# due.net
KiCad netlist of a schematic drawn in EAGLE
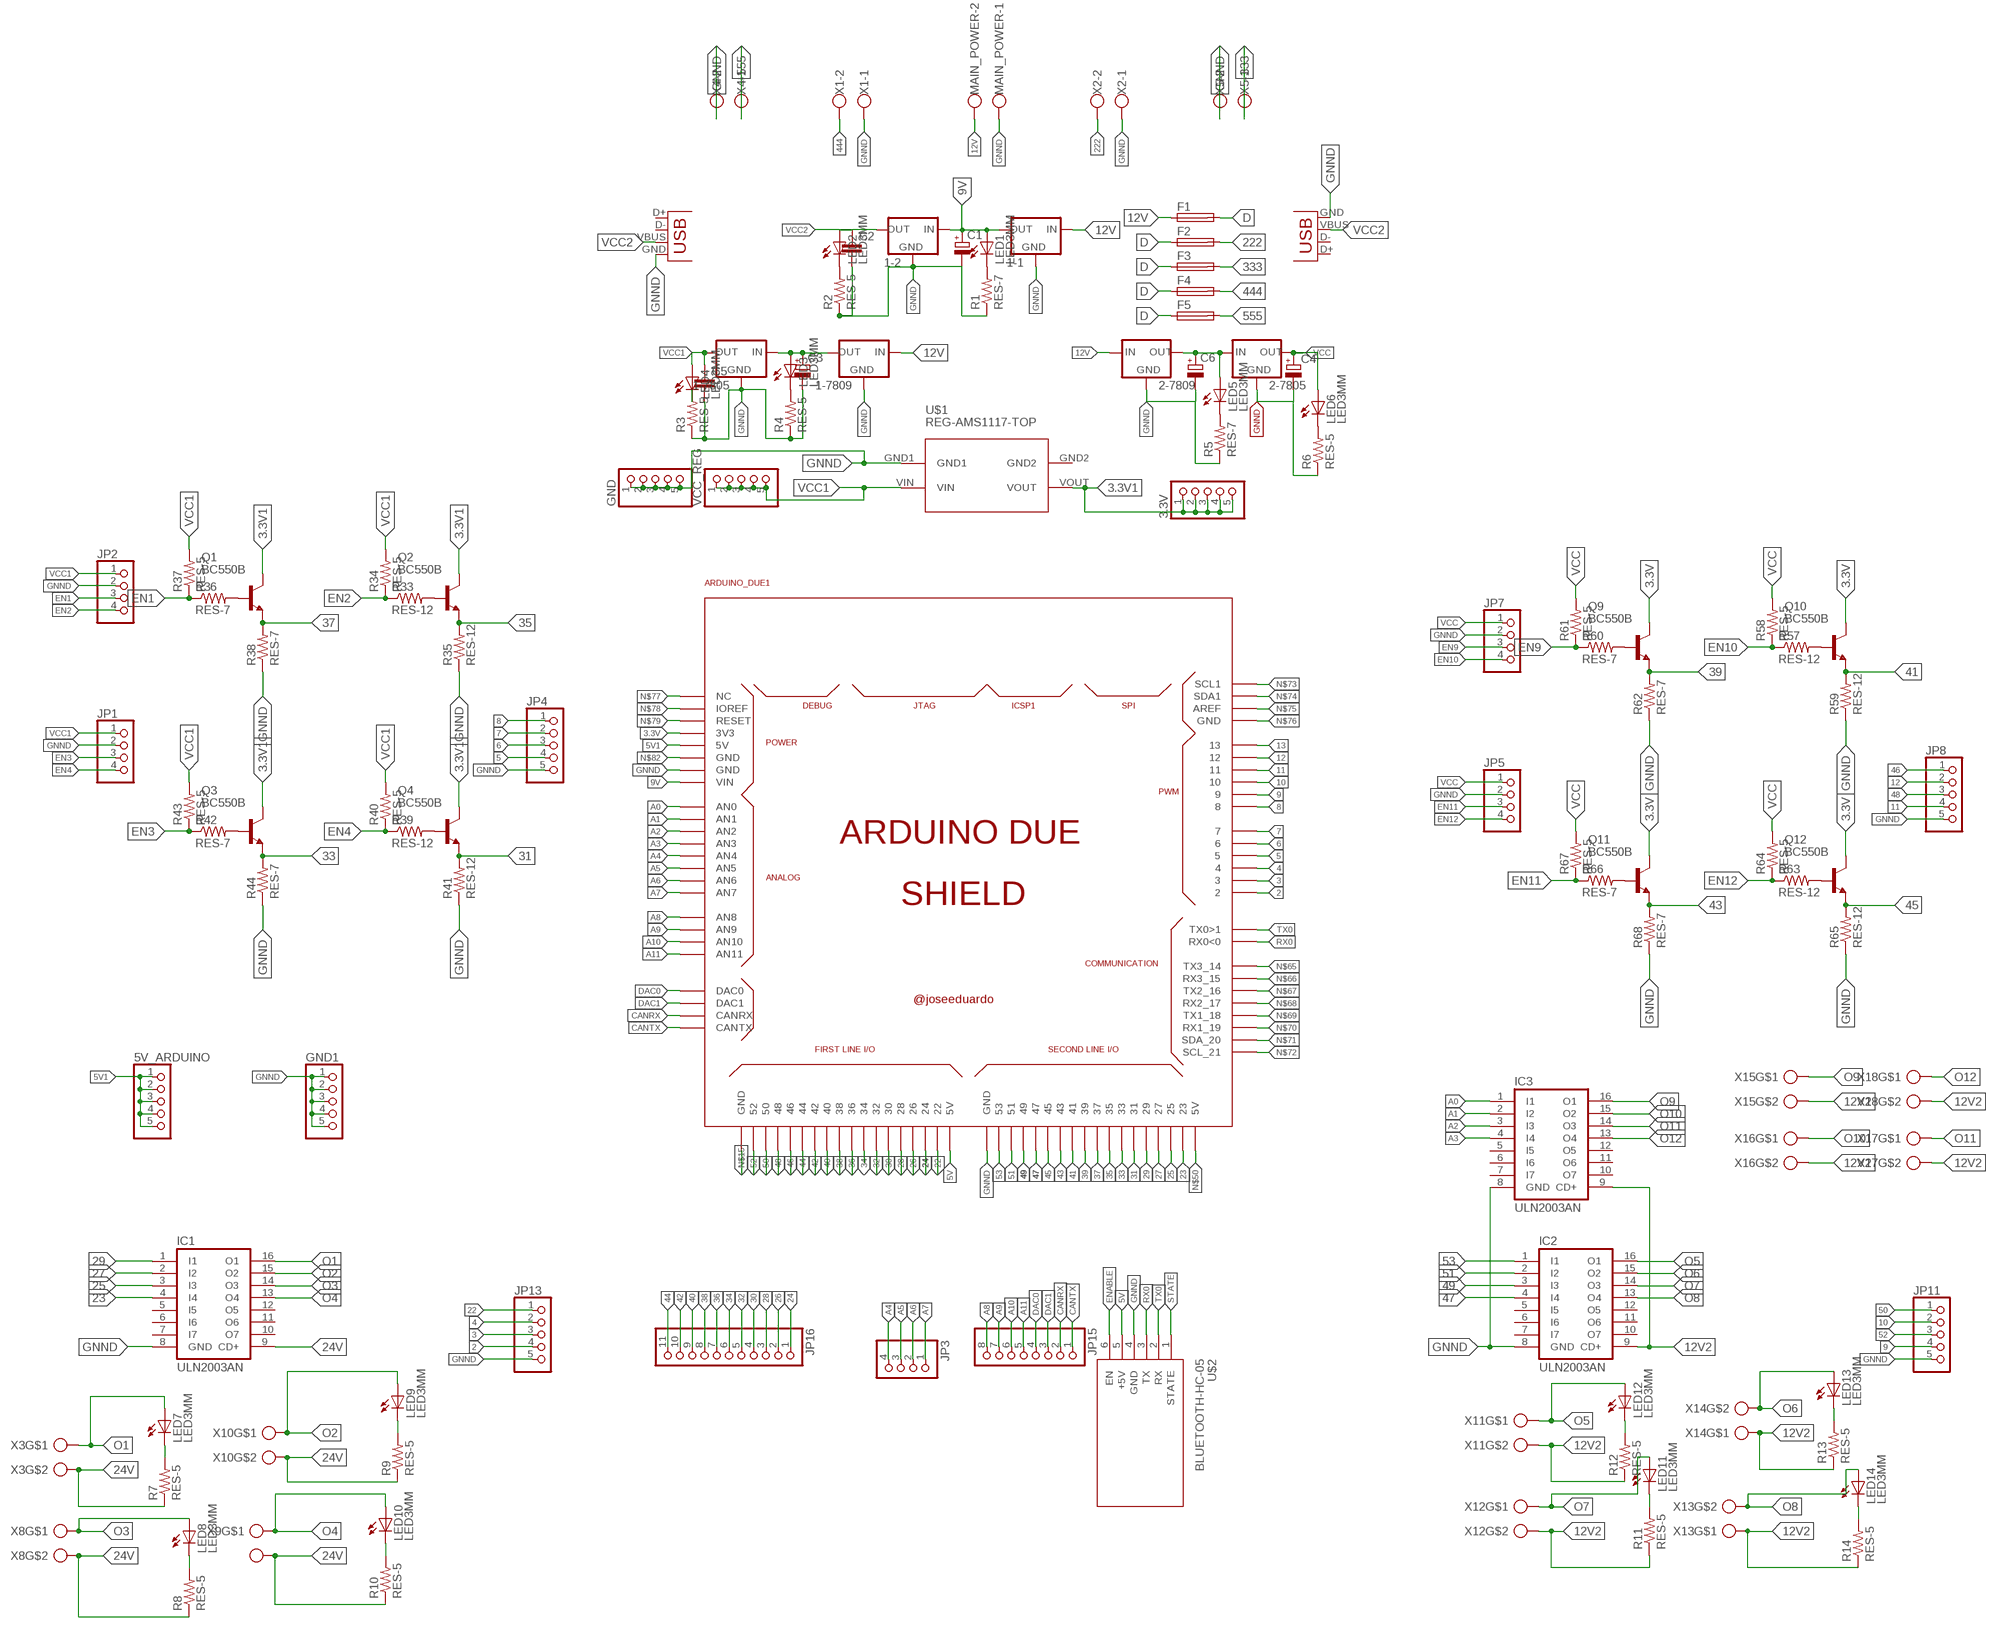
[diagram p0: schematic, sheet 1]

(export (version "E")
  (design (tool "Eeschema 10.0.6"))
  (components
    (comp (ref "1-1")
      (value "78XXS")
      (footprint "eagle-import:78XXS")
      (libsource (lib "eagle-import") (part "78XXS"))
    )
    (comp (ref "1-2")
      (value "78XXS")
      (footprint "eagle-import:78XXS")
      (libsource (lib "eagle-import") (part "78XXS"))
    )
    (comp (ref "1-7805")
      (value "78XXS")
      (footprint "eagle-import:78XXS")
      (libsource (lib "eagle-import") (part "78XXS"))
    )
    (comp (ref "1-7809")
      (value "78XXS")
      (footprint "eagle-import:78XXS")
      (libsource (lib "eagle-import") (part "78XXS"))
    )
    (comp (ref "2-7805")
      (value "78XXS")
      (footprint "eagle-import:78XXS")
      (libsource (lib "eagle-import") (part "78XXS"))
    )
    (comp (ref "2-7809")
      (value "78XXS")
      (footprint "eagle-import:78XXS")
      (libsource (lib "eagle-import") (part "78XXS"))
    )
    (comp (ref "3.3V")
      (value "PINHD-1X5")
      (footprint "eagle-import:1X05")
      (libsource (lib "eagle-import") (part "PINHD-1X5"))
    )
    (comp (ref "5V_ARDUINO")
      (value "PINHD-1X5")
      (footprint "eagle-import:1X05")
      (libsource (lib "eagle-import") (part "PINHD-1X5"))
    )
    (comp (ref "ARDUINO_DUE1")
      (value "ARDUINO_DUE_SHIELD")
      (footprint "eagle-import:ARDUINO_DUE_SHIELD")
      (libsource (lib "eagle-import") (part "ARDUINO_DUE_SHIELD"))
    )
    (comp (ref "C1")
      (value "CAP_POL")
      (footprint "eagle-import:E3,5-8")
      (libsource (lib "eagle-import") (part "CAP_POL"))
    )
    (comp (ref "C2")
      (value "CAPACITOR")
      (footprint "eagle-import:C025-025X050")
      (libsource (lib "eagle-import") (part "CAPACITOR"))
    )
    (comp (ref "C3")
      (value "CAP_POL")
      (footprint "eagle-import:E3,5-8")
      (libsource (lib "eagle-import") (part "CAP_POL"))
    )
    (comp (ref "C4")
      (value "CAP_POL")
      (footprint "eagle-import:E3,5-8")
      (libsource (lib "eagle-import") (part "CAP_POL"))
    )
    (comp (ref "C5")
      (value "CAPACITOR")
      (footprint "eagle-import:C025-025X050")
      (libsource (lib "eagle-import") (part "CAPACITOR"))
    )
    (comp (ref "C6")
      (value "CAP_POL")
      (footprint "eagle-import:E3,5-8")
      (libsource (lib "eagle-import") (part "CAP_POL"))
    )
    (comp (ref "F1")
      (value "FUSE_HOLDER")
      (footprint "eagle-import:SH22,5A")
      (libsource (lib "eagle-import") (part "FUSE_HOLDER"))
    )
    (comp (ref "F2")
      (value "FUSE_HOLDER")
      (footprint "eagle-import:SH22,5A")
      (libsource (lib "eagle-import") (part "FUSE_HOLDER"))
    )
    (comp (ref "F3")
      (value "FUSE_HOLDER")
      (footprint "eagle-import:SH22,5A")
      (libsource (lib "eagle-import") (part "FUSE_HOLDER"))
    )
    (comp (ref "F4")
      (value "FUSE_HOLDER")
      (footprint "eagle-import:SH22,5A")
      (libsource (lib "eagle-import") (part "FUSE_HOLDER"))
    )
    (comp (ref "F5")
      (value "FUSE_HOLDER")
      (footprint "eagle-import:SH22,5A")
      (libsource (lib "eagle-import") (part "FUSE_HOLDER"))
    )
    (comp (ref "GND")
      (value "PINHD-1X5")
      (footprint "eagle-import:1X05")
      (libsource (lib "eagle-import") (part "PINHD-1X5"))
    )
    (comp (ref "GND1")
      (value "PINHD-1X5")
      (footprint "eagle-import:1X05")
      (libsource (lib "eagle-import") (part "PINHD-1X5"))
    )
    (comp (ref "IC1")
      (value "ULN2003AN")
      (footprint "eagle-import:DIL16")
      (libsource (lib "eagle-import") (part "ULN2003AN"))
    )
    (comp (ref "IC2")
      (value "ULN2003AN")
      (footprint "eagle-import:DIL16")
      (libsource (lib "eagle-import") (part "ULN2003AN"))
    )
    (comp (ref "IC3")
      (value "ULN2003AN")
      (footprint "eagle-import:DIL16")
      (libsource (lib "eagle-import") (part "ULN2003AN"))
    )
    (comp (ref "JP1")
      (value "PINHD-1X4")
      (footprint "eagle-import:1X04")
      (libsource (lib "eagle-import") (part "PINHD-1X4"))
    )
    (comp (ref "JP2")
      (value "PINHD-1X4")
      (footprint "eagle-import:1X04")
      (libsource (lib "eagle-import") (part "PINHD-1X4"))
    )
    (comp (ref "JP3")
      (value "PINHD-1X4")
      (footprint "eagle-import:1X04")
      (libsource (lib "eagle-import") (part "PINHD-1X4"))
    )
    (comp (ref "JP4")
      (value "PINHD-1X5")
      (footprint "eagle-import:1X05")
      (libsource (lib "eagle-import") (part "PINHD-1X5"))
    )
    (comp (ref "JP5")
      (value "PINHD-1X4")
      (footprint "eagle-import:1X04")
      (libsource (lib "eagle-import") (part "PINHD-1X4"))
    )
    (comp (ref "JP7")
      (value "PINHD-1X4")
      (footprint "eagle-import:1X04")
      (libsource (lib "eagle-import") (part "PINHD-1X4"))
    )
    (comp (ref "JP8")
      (value "PINHD-1X5")
      (footprint "eagle-import:1X05")
      (libsource (lib "eagle-import") (part "PINHD-1X5"))
    )
    (comp (ref "JP11")
      (value "PINHD-1X5")
      (footprint "eagle-import:1X05")
      (libsource (lib "eagle-import") (part "PINHD-1X5"))
    )
    (comp (ref "JP13")
      (value "PINHD-1X5")
      (footprint "eagle-import:1X05")
      (libsource (lib "eagle-import") (part "PINHD-1X5"))
    )
    (comp (ref "JP15")
      (value "PINHD-1X8")
      (footprint "eagle-import:1X08")
      (libsource (lib "eagle-import") (part "PINHD-1X8"))
    )
    (comp (ref "JP16")
      (value "PINHD-1X11")
      (footprint "eagle-import:1X11")
      (libsource (lib "eagle-import") (part "PINHD-1X11"))
    )
    (comp (ref "LED1")
      (value "LED3MM")
      (footprint "eagle-import:LED3MM")
      (libsource (lib "eagle-import") (part "LED3MM"))
    )
    (comp (ref "LED2")
      (value "LED3MM")
      (footprint "eagle-import:LED3MM")
      (libsource (lib "eagle-import") (part "LED3MM"))
    )
    (comp (ref "LED3")
      (value "LED3MM")
      (footprint "eagle-import:LED3MM")
      (libsource (lib "eagle-import") (part "LED3MM"))
    )
    (comp (ref "LED4")
      (value "LED3MM")
      (footprint "eagle-import:LED3MM")
      (libsource (lib "eagle-import") (part "LED3MM"))
    )
    (comp (ref "LED5")
      (value "LED3MM")
      (footprint "eagle-import:LED3MM")
      (libsource (lib "eagle-import") (part "LED3MM"))
    )
    (comp (ref "LED6")
      (value "LED3MM")
      (footprint "eagle-import:LED3MM")
      (libsource (lib "eagle-import") (part "LED3MM"))
    )
    (comp (ref "LED7")
      (value "LED3MM")
      (footprint "eagle-import:LED3MM")
      (libsource (lib "eagle-import") (part "LED3MM"))
    )
    (comp (ref "LED8")
      (value "LED3MM")
      (footprint "eagle-import:LED3MM")
      (libsource (lib "eagle-import") (part "LED3MM"))
    )
    (comp (ref "LED9")
      (value "LED3MM")
      (footprint "eagle-import:LED3MM")
      (libsource (lib "eagle-import") (part "LED3MM"))
    )
    (comp (ref "LED10")
      (value "LED3MM")
      (footprint "eagle-import:LED3MM")
      (libsource (lib "eagle-import") (part "LED3MM"))
    )
    (comp (ref "LED11")
      (value "LED3MM")
      (footprint "eagle-import:LED3MM")
      (libsource (lib "eagle-import") (part "LED3MM"))
    )
    (comp (ref "LED12")
      (value "LED3MM")
      (footprint "eagle-import:LED3MM")
      (libsource (lib "eagle-import") (part "LED3MM"))
    )
    (comp (ref "LED13")
      (value "LED3MM")
      (footprint "eagle-import:LED3MM")
      (libsource (lib "eagle-import") (part "LED3MM"))
    )
    (comp (ref "LED14")
      (value "LED3MM")
      (footprint "eagle-import:LED3MM")
      (libsource (lib "eagle-import") (part "LED3MM"))
    )
    (comp (ref "MAIN_POWER")
      (value "ROSTA.POWER")
      (footprint "eagle-import:W239-302")
      (libsource (lib "eagle-import") (part "ROSTA.POWER"))
    )
    (comp (ref "Q1")
      (value "BC550B")
      (footprint "eagle-import:TO92-EBC")
      (libsource (lib "eagle-import") (part "BC550B"))
    )
    (comp (ref "Q2")
      (value "BC550B")
      (footprint "eagle-import:TO92-EBC")
      (libsource (lib "eagle-import") (part "BC550B"))
    )
    (comp (ref "Q3")
      (value "BC550B")
      (footprint "eagle-import:TO92-EBC")
      (libsource (lib "eagle-import") (part "BC550B"))
    )
    (comp (ref "Q4")
      (value "BC550B")
      (footprint "eagle-import:TO92-EBC")
      (libsource (lib "eagle-import") (part "BC550B"))
    )
    (comp (ref "Q9")
      (value "BC550B")
      (footprint "eagle-import:TO92-EBC")
      (libsource (lib "eagle-import") (part "BC550B"))
    )
    (comp (ref "Q10")
      (value "BC550B")
      (footprint "eagle-import:TO92-EBC")
      (libsource (lib "eagle-import") (part "BC550B"))
    )
    (comp (ref "Q11")
      (value "BC550B")
      (footprint "eagle-import:TO92-EBC")
      (libsource (lib "eagle-import") (part "BC550B"))
    )
    (comp (ref "Q12")
      (value "BC550B")
      (footprint "eagle-import:TO92-EBC")
      (libsource (lib "eagle-import") (part "BC550B"))
    )
    (comp (ref "R1")
      (value "RES-7")
      (footprint "eagle-import:0204_7")
      (libsource (lib "eagle-import") (part "RES-7"))
    )
    (comp (ref "R2")
      (value "RES-5")
      (footprint "eagle-import:0204_5")
      (libsource (lib "eagle-import") (part "RES-5"))
    )
    (comp (ref "R3")
      (value "RES-5")
      (footprint "eagle-import:0204_5")
      (libsource (lib "eagle-import") (part "RES-5"))
    )
    (comp (ref "R4")
      (value "RES-5")
      (footprint "eagle-import:0204_5")
      (libsource (lib "eagle-import") (part "RES-5"))
    )
    (comp (ref "R5")
      (value "RES-7")
      (footprint "eagle-import:0204_7")
      (libsource (lib "eagle-import") (part "RES-7"))
    )
    (comp (ref "R6")
      (value "RES-5")
      (footprint "eagle-import:0204_5")
      (libsource (lib "eagle-import") (part "RES-5"))
    )
    (comp (ref "R7")
      (value "RES-5")
      (footprint "eagle-import:0204_5")
      (libsource (lib "eagle-import") (part "RES-5"))
    )
    (comp (ref "R8")
      (value "RES-5")
      (footprint "eagle-import:0204_5")
      (libsource (lib "eagle-import") (part "RES-5"))
    )
    (comp (ref "R9")
      (value "RES-5")
      (footprint "eagle-import:0204_5")
      (libsource (lib "eagle-import") (part "RES-5"))
    )
    (comp (ref "R10")
      (value "RES-5")
      (footprint "eagle-import:0204_5")
      (libsource (lib "eagle-import") (part "RES-5"))
    )
    (comp (ref "R11")
      (value "RES-5")
      (footprint "eagle-import:0204_5")
      (libsource (lib "eagle-import") (part "RES-5"))
    )
    (comp (ref "R12")
      (value "RES-5")
      (footprint "eagle-import:0204_5")
      (libsource (lib "eagle-import") (part "RES-5"))
    )
    (comp (ref "R13")
      (value "RES-5")
      (footprint "eagle-import:0204_5")
      (libsource (lib "eagle-import") (part "RES-5"))
    )
    (comp (ref "R14")
      (value "RES-5")
      (footprint "eagle-import:0204_5")
      (libsource (lib "eagle-import") (part "RES-5"))
    )
    (comp (ref "R33")
      (value "RES-12")
      (footprint "eagle-import:0207_12")
      (libsource (lib "eagle-import") (part "RES-12"))
    )
    (comp (ref "R34")
      (value "RES-5")
      (footprint "eagle-import:0204_5")
      (libsource (lib "eagle-import") (part "RES-5"))
    )
    (comp (ref "R35")
      (value "RES-12")
      (footprint "eagle-import:0207_12")
      (libsource (lib "eagle-import") (part "RES-12"))
    )
    (comp (ref "R36")
      (value "RES-7")
      (footprint "eagle-import:0204_7")
      (libsource (lib "eagle-import") (part "RES-7"))
    )
    (comp (ref "R37")
      (value "RES-5")
      (footprint "eagle-import:0204_5")
      (libsource (lib "eagle-import") (part "RES-5"))
    )
    (comp (ref "R38")
      (value "RES-7")
      (footprint "eagle-import:0204_7")
      (libsource (lib "eagle-import") (part "RES-7"))
    )
    (comp (ref "R39")
      (value "RES-12")
      (footprint "eagle-import:0207_12")
      (libsource (lib "eagle-import") (part "RES-12"))
    )
    (comp (ref "R40")
      (value "RES-5")
      (footprint "eagle-import:0204_5")
      (libsource (lib "eagle-import") (part "RES-5"))
    )
    (comp (ref "R41")
      (value "RES-12")
      (footprint "eagle-import:0207_12")
      (libsource (lib "eagle-import") (part "RES-12"))
    )
    (comp (ref "R42")
      (value "RES-7")
      (footprint "eagle-import:0204_7")
      (libsource (lib "eagle-import") (part "RES-7"))
    )
    (comp (ref "R43")
      (value "RES-5")
      (footprint "eagle-import:0204_5")
      (libsource (lib "eagle-import") (part "RES-5"))
    )
    (comp (ref "R44")
      (value "RES-7")
      (footprint "eagle-import:0204_7")
      (libsource (lib "eagle-import") (part "RES-7"))
    )
    (comp (ref "R57")
      (value "RES-12")
      (footprint "eagle-import:0207_12")
      (libsource (lib "eagle-import") (part "RES-12"))
    )
    (comp (ref "R58")
      (value "RES-5")
      (footprint "eagle-import:0204_5")
      (libsource (lib "eagle-import") (part "RES-5"))
    )
    (comp (ref "R59")
      (value "RES-12")
      (footprint "eagle-import:0207_12")
      (libsource (lib "eagle-import") (part "RES-12"))
    )
    (comp (ref "R60")
      (value "RES-7")
      (footprint "eagle-import:0204_7")
      (libsource (lib "eagle-import") (part "RES-7"))
    )
    (comp (ref "R61")
      (value "RES-5")
      (footprint "eagle-import:0204_5")
      (libsource (lib "eagle-import") (part "RES-5"))
    )
    (comp (ref "R62")
      (value "RES-7")
      (footprint "eagle-import:0204_7")
      (libsource (lib "eagle-import") (part "RES-7"))
    )
    (comp (ref "R63")
      (value "RES-12")
      (footprint "eagle-import:0207_12")
      (libsource (lib "eagle-import") (part "RES-12"))
    )
    (comp (ref "R64")
      (value "RES-5")
      (footprint "eagle-import:0204_5")
      (libsource (lib "eagle-import") (part "RES-5"))
    )
    (comp (ref "R65")
      (value "RES-12")
      (footprint "eagle-import:0207_12")
      (libsource (lib "eagle-import") (part "RES-12"))
    )
    (comp (ref "R66")
      (value "RES-7")
      (footprint "eagle-import:0204_7")
      (libsource (lib "eagle-import") (part "RES-7"))
    )
    (comp (ref "R67")
      (value "RES-5")
      (footprint "eagle-import:0204_5")
      (libsource (lib "eagle-import") (part "RES-5"))
    )
    (comp (ref "R68")
      (value "RES-7")
      (footprint "eagle-import:0204_7")
      (libsource (lib "eagle-import") (part "RES-7"))
    )
    (comp (ref "U$1")
      (value "REG-AMS1117-TOP")
      (footprint "eagle-import:REG-AMS1117_TOP")
      (libsource (lib "eagle-import") (part "REG-AMS1117-TOP"))
    )
    (comp (ref "U$2")
      (value "BLUETOOTH-HC-05")
      (footprint "eagle-import:WIRELESS-BLUETOOTH-HC-05")
      (libsource (lib "eagle-import") (part "BLUETOOTH-HC-05"))
    )
    (comp (ref "VCC_REG")
      (value "PINHD-1X5")
      (footprint "eagle-import:1X05")
      (libsource (lib "eagle-import") (part "PINHD-1X5"))
    )
    (comp (ref "X1")
      (value "ROSTA.POWER")
      (footprint "eagle-import:W239-302")
      (libsource (lib "eagle-import") (part "ROSTA.POWER"))
    )
    (comp (ref "X2")
      (value "ROSTA.POWER")
      (footprint "eagle-import:W239-302")
      (libsource (lib "eagle-import") (part "ROSTA.POWER"))
    )
    (comp (ref "X3")
      (value "CON_PTR_2")
      (footprint "eagle-import:AK300_2")
      (libsource (lib "eagle-import") (part "CON_PTR_2"))
    )
    (comp (ref "X4")
      (value "ROSTA.POWER")
      (footprint "eagle-import:W239-302")
      (libsource (lib "eagle-import") (part "ROSTA.POWER"))
    )
    (comp (ref "X5")
      (value "ROSTA.POWER")
      (footprint "eagle-import:W239-302")
      (libsource (lib "eagle-import") (part "ROSTA.POWER"))
    )
    (comp (ref "X6")
      (value "USB-A-H")
      (footprint "eagle-import:USB-A-H")
      (libsource (lib "eagle-import") (part "USB-A-H"))
    )
    (comp (ref "X7")
      (value "USB-A-H")
      (footprint "eagle-import:USB-A-H")
      (libsource (lib "eagle-import") (part "USB-A-H"))
    )
    (comp (ref "X8")
      (value "CON_PTR_2")
      (footprint "eagle-import:AK300_2")
      (libsource (lib "eagle-import") (part "CON_PTR_2"))
    )
    (comp (ref "X9")
      (value "CON_PTR_2")
      (footprint "eagle-import:AK300_2")
      (libsource (lib "eagle-import") (part "CON_PTR_2"))
    )
    (comp (ref "X10")
      (value "CON_PTR_2")
      (footprint "eagle-import:AK300_2")
      (libsource (lib "eagle-import") (part "CON_PTR_2"))
    )
    (comp (ref "X11")
      (value "CON_PTR_2")
      (footprint "eagle-import:AK300_2")
      (libsource (lib "eagle-import") (part "CON_PTR_2"))
    )
    (comp (ref "X12")
      (value "CON_PTR_2")
      (footprint "eagle-import:AK300_2")
      (libsource (lib "eagle-import") (part "CON_PTR_2"))
    )
    (comp (ref "X13")
      (value "CON_PTR_2")
      (footprint "eagle-import:AK300_2")
      (libsource (lib "eagle-import") (part "CON_PTR_2"))
    )
    (comp (ref "X14")
      (value "CON_PTR_2")
      (footprint "eagle-import:AK300_2")
      (libsource (lib "eagle-import") (part "CON_PTR_2"))
    )
    (comp (ref "X15")
      (value "CON_PTR_2")
      (footprint "eagle-import:AK300_2")
      (libsource (lib "eagle-import") (part "CON_PTR_2"))
    )
    (comp (ref "X16")
      (value "CON_PTR_2")
      (footprint "eagle-import:AK300_2")
      (libsource (lib "eagle-import") (part "CON_PTR_2"))
    )
    (comp (ref "X17")
      (value "CON_PTR_2")
      (footprint "eagle-import:AK300_2")
      (libsource (lib "eagle-import") (part "CON_PTR_2"))
    )
    (comp (ref "X18")
      (value "CON_PTR_2")
      (footprint "eagle-import:AK300_2")
      (libsource (lib "eagle-import") (part "CON_PTR_2"))
    )
  )
  (nets
    (net (code "1") (name "2") (class "Default")
      (node (ref "ARDUINO_DUE1") (pin "2") (pinfunction "2_2") (pintype "bidirectional"))
      (node (ref "JP13") (pin "4") (pinfunction "4_4") (pintype "passive"))
    )
    (net (code "2") (name "3") (class "Default")
      (node (ref "ARDUINO_DUE1") (pin "3") (pinfunction "3_3") (pintype "bidirectional"))
      (node (ref "JP13") (pin "3") (pinfunction "3_3") (pintype "passive"))
    )
    (net (code "3") (name "3.3V") (class "Default")
      (node (ref "ARDUINO_DUE1") (pin "3V3") (pinfunction "3V3_3V3") (pintype "bidirectional"))
      (node (ref "Q10") (pin "C") (pinfunction "C_C") (pintype "passive"))
      (node (ref "Q11") (pin "C") (pinfunction "C_C") (pintype "passive"))
      (node (ref "Q12") (pin "C") (pinfunction "C_C") (pintype "passive"))
      (node (ref "Q9") (pin "C") (pinfunction "C_C") (pintype "passive"))
    )
    (net (code "4") (name "3.3V1") (class "Default")
      (node (ref "3.3V") (pin "1") (pinfunction "1_1") (pintype "passive"))
      (node (ref "3.3V") (pin "2") (pinfunction "2_2") (pintype "passive"))
      (node (ref "3.3V") (pin "3") (pinfunction "3_3") (pintype "passive"))
      (node (ref "3.3V") (pin "4") (pinfunction "4_4") (pintype "passive"))
      (node (ref "3.3V") (pin "5") (pinfunction "5_5") (pintype "passive"))
      (node (ref "Q1") (pin "C") (pinfunction "C_C") (pintype "passive"))
      (node (ref "Q2") (pin "C") (pinfunction "C_C") (pintype "passive"))
      (node (ref "Q3") (pin "C") (pinfunction "C_C") (pintype "passive"))
      (node (ref "Q4") (pin "C") (pinfunction "C_C") (pintype "passive"))
      (node (ref "U$1") (pin "VOUT") (pinfunction "VOUT_VOUT") (pintype "bidirectional"))
    )
    (net (code "5") (name "4") (class "Default")
      (node (ref "ARDUINO_DUE1") (pin "4") (pinfunction "4_4") (pintype "bidirectional"))
      (node (ref "JP13") (pin "2") (pinfunction "2_2") (pintype "passive"))
    )
    (net (code "6") (name "5") (class "Default")
      (node (ref "ARDUINO_DUE1") (pin "5") (pinfunction "5_5") (pintype "bidirectional"))
      (node (ref "JP4") (pin "4") (pinfunction "4_4") (pintype "passive"))
    )
    (net (code "7") (name "5V") (class "Default")
      (node (ref "ARDUINO_DUE1") (pin "5V0_1") (pinfunction "5V_5V0_1") (pintype "bidirectional"))
      (node (ref "U$2") (pin "5") (pinfunction "+5V_5") (pintype "power_in"))
    )
    (net (code "8") (name "5V1") (class "Default")
      (node (ref "5V_ARDUINO") (pin "1") (pinfunction "1_1") (pintype "passive"))
      (node (ref "5V_ARDUINO") (pin "2") (pinfunction "2_2") (pintype "passive"))
      (node (ref "5V_ARDUINO") (pin "3") (pinfunction "3_3") (pintype "passive"))
      (node (ref "5V_ARDUINO") (pin "4") (pinfunction "4_4") (pintype "passive"))
      (node (ref "5V_ARDUINO") (pin "5") (pinfunction "5_5") (pintype "passive"))
      (node (ref "ARDUINO_DUE1") (pin "5V0") (pinfunction "5V_5V0") (pintype "bidirectional"))
    )
    (net (code "9") (name "6") (class "Default")
      (node (ref "ARDUINO_DUE1") (pin "6") (pinfunction "6_6") (pintype "bidirectional"))
      (node (ref "JP4") (pin "3") (pinfunction "3_3") (pintype "passive"))
    )
    (net (code "10") (name "7") (class "Default")
      (node (ref "ARDUINO_DUE1") (pin "7") (pinfunction "7_7") (pintype "bidirectional"))
      (node (ref "JP4") (pin "2") (pinfunction "2_2") (pintype "passive"))
    )
    (net (code "11") (name "8") (class "Default")
      (node (ref "ARDUINO_DUE1") (pin "8") (pinfunction "8_8") (pintype "bidirectional"))
      (node (ref "JP4") (pin "1") (pinfunction "1_1") (pintype "passive"))
    )
    (net (code "12") (name "9") (class "Default")
      (node (ref "ARDUINO_DUE1") (pin "9") (pinfunction "9_9") (pintype "bidirectional"))
      (node (ref "JP11") (pin "4") (pinfunction "4_4") (pintype "passive"))
    )
    (net (code "13") (name "9V") (class "Default")
      (node (ref "1-1") (pin "OUT") (pinfunction "OUT_OUT") (pintype "passive"))
      (node (ref "1-2") (pin "IN") (pinfunction "IN_IN") (pintype "input"))
      (node (ref "ARDUINO_DUE1") (pin "VIN") (pinfunction "VIN_VIN") (pintype "bidirectional"))
      (node (ref "C1") (pin "+") (pinfunction "+_+") (pintype "passive"))
      (node (ref "LED1") (pin "A") (pinfunction "A_A") (pintype "passive"))
    )
    (net (code "14") (name "10") (class "Default")
      (node (ref "ARDUINO_DUE1") (pin "10") (pinfunction "10_10") (pintype "bidirectional"))
      (node (ref "JP11") (pin "2") (pinfunction "2_2") (pintype "passive"))
    )
    (net (code "15") (name "11") (class "Default")
      (node (ref "ARDUINO_DUE1") (pin "11") (pinfunction "11_11") (pintype "bidirectional"))
      (node (ref "JP8") (pin "4") (pinfunction "4_4") (pintype "passive"))
    )
    (net (code "16") (name "12") (class "Default")
      (node (ref "ARDUINO_DUE1") (pin "12") (pinfunction "12_12") (pintype "bidirectional"))
      (node (ref "JP8") (pin "2") (pinfunction "2_2") (pintype "passive"))
    )
    (net (code "17") (name "12V") (class "Default")
      (node (ref "1-1") (pin "IN") (pinfunction "IN_IN") (pintype "input"))
      (node (ref "1-7809") (pin "IN") (pinfunction "IN_IN") (pintype "input"))
      (node (ref "2-7809") (pin "IN") (pinfunction "IN_IN") (pintype "input"))
      (node (ref "F1") (pin "1") (pinfunction "1_1") (pintype "passive"))
      (node (ref "MAIN_POWER") (pin "2") (pinfunction "KL_2") (pintype "passive"))
    )
    (net (code "18") (name "12V2") (class "Default")
      (node (ref "IC2") (pin "9") (pinfunction "CD+_9") (pintype "passive"))
      (node (ref "IC3") (pin "9") (pinfunction "CD+_9") (pintype "passive"))
      (node (ref "R11") (pin "1") (pinfunction "1_1") (pintype "passive"))
      (node (ref "R12") (pin "1") (pinfunction "1_1") (pintype "passive"))
      (node (ref "R13") (pin "1") (pinfunction "1_1") (pintype "passive"))
      (node (ref "R14") (pin "1") (pinfunction "1_1") (pintype "passive"))
      (node (ref "X11") (pin "2") (pinfunction "KL_2") (pintype "passive"))
      (node (ref "X12") (pin "2") (pinfunction "KL_2") (pintype "passive"))
      (node (ref "X13") (pin "1") (pinfunction "KL_1") (pintype "passive"))
      (node (ref "X14") (pin "1") (pinfunction "KL_1") (pintype "passive"))
      (node (ref "X15") (pin "2") (pinfunction "KL_2") (pintype "passive"))
      (node (ref "X16") (pin "2") (pinfunction "KL_2") (pintype "passive"))
      (node (ref "X17") (pin "2") (pinfunction "KL_2") (pintype "passive"))
      (node (ref "X18") (pin "2") (pinfunction "KL_2") (pintype "passive"))
    )
    (net (code "19") (name "13") (class "Default")
      (node (ref "ARDUINO_DUE1") (pin "13") (pinfunction "13_13") (pintype "bidirectional"))
    )
    (net (code "20") (name "22") (class "Default")
      (node (ref "ARDUINO_DUE1") (pin "22") (pinfunction "22_22") (pintype "bidirectional"))
      (node (ref "JP13") (pin "1") (pinfunction "1_1") (pintype "passive"))
    )
    (net (code "21") (name "23") (class "Default")
      (node (ref "ARDUINO_DUE1") (pin "23") (pinfunction "23_23") (pintype "bidirectional"))
      (node (ref "IC1") (pin "4") (pinfunction "I4_4") (pintype "input"))
    )
    (net (code "22") (name "24") (class "Default")
      (node (ref "ARDUINO_DUE1") (pin "24") (pinfunction "24_24") (pintype "bidirectional"))
      (node (ref "JP16") (pin "1") (pinfunction "1_1") (pintype "passive"))
    )
    (net (code "23") (name "24V") (class "Default")
      (node (ref "IC1") (pin "9") (pinfunction "CD+_9") (pintype "passive"))
      (node (ref "R10") (pin "1") (pinfunction "1_1") (pintype "passive"))
      (node (ref "R7") (pin "1") (pinfunction "1_1") (pintype "passive"))
      (node (ref "R8") (pin "1") (pinfunction "1_1") (pintype "passive"))
      (node (ref "R9") (pin "1") (pinfunction "1_1") (pintype "passive"))
      (node (ref "X10") (pin "2") (pinfunction "KL_2") (pintype "passive"))
      (node (ref "X3") (pin "2") (pinfunction "KL_2") (pintype "passive"))
      (node (ref "X8") (pin "2") (pinfunction "KL_2") (pintype "passive"))
      (node (ref "X9") (pin "2") (pinfunction "KL_2") (pintype "passive"))
    )
    (net (code "24") (name "25") (class "Default")
      (node (ref "ARDUINO_DUE1") (pin "25") (pinfunction "25_25") (pintype "bidirectional"))
      (node (ref "IC1") (pin "3") (pinfunction "I3_3") (pintype "input"))
    )
    (net (code "25") (name "26") (class "Default")
      (node (ref "ARDUINO_DUE1") (pin "26") (pinfunction "26_26") (pintype "bidirectional"))
      (node (ref "JP16") (pin "2") (pinfunction "2_2") (pintype "passive"))
    )
    (net (code "26") (name "27") (class "Default")
      (node (ref "ARDUINO_DUE1") (pin "27") (pinfunction "27_27") (pintype "bidirectional"))
      (node (ref "IC1") (pin "2") (pinfunction "I2_2") (pintype "input"))
    )
    (net (code "27") (name "28") (class "Default")
      (node (ref "ARDUINO_DUE1") (pin "28") (pinfunction "28_28") (pintype "bidirectional"))
      (node (ref "JP16") (pin "3") (pinfunction "3_3") (pintype "passive"))
    )
    (net (code "28") (name "29") (class "Default")
      (node (ref "ARDUINO_DUE1") (pin "29") (pinfunction "29_29") (pintype "bidirectional"))
      (node (ref "IC1") (pin "1") (pinfunction "I1_1") (pintype "input"))
    )
    (net (code "29") (name "30") (class "Default")
      (node (ref "ARDUINO_DUE1") (pin "30") (pinfunction "30_30") (pintype "bidirectional"))
      (node (ref "JP16") (pin "4") (pinfunction "4_4") (pintype "passive"))
    )
    (net (code "30") (name "31") (class "Default")
      (node (ref "ARDUINO_DUE1") (pin "31") (pinfunction "31_31") (pintype "bidirectional"))
      (node (ref "Q4") (pin "E") (pinfunction "E_E") (pintype "passive"))
      (node (ref "R41") (pin "2") (pinfunction "2_2") (pintype "passive"))
    )
    (net (code "31") (name "32") (class "Default")
      (node (ref "ARDUINO_DUE1") (pin "32") (pinfunction "32_32") (pintype "bidirectional"))
      (node (ref "JP16") (pin "5") (pinfunction "5_5") (pintype "passive"))
    )
    (net (code "32") (name "33") (class "Default")
      (node (ref "ARDUINO_DUE1") (pin "33") (pinfunction "33_33") (pintype "bidirectional"))
      (node (ref "Q3") (pin "E") (pinfunction "E_E") (pintype "passive"))
      (node (ref "R44") (pin "2") (pinfunction "2_2") (pintype "passive"))
    )
    (net (code "33") (name "34") (class "Default")
      (node (ref "ARDUINO_DUE1") (pin "34") (pinfunction "34_34") (pintype "bidirectional"))
      (node (ref "JP16") (pin "6") (pinfunction "6_6") (pintype "passive"))
    )
    (net (code "34") (name "35") (class "Default")
      (node (ref "ARDUINO_DUE1") (pin "35") (pinfunction "35_35") (pintype "bidirectional"))
      (node (ref "Q2") (pin "E") (pinfunction "E_E") (pintype "passive"))
      (node (ref "R35") (pin "2") (pinfunction "2_2") (pintype "passive"))
    )
    (net (code "35") (name "36") (class "Default")
      (node (ref "ARDUINO_DUE1") (pin "36") (pinfunction "36_36") (pintype "bidirectional"))
      (node (ref "JP16") (pin "7") (pinfunction "7_7") (pintype "passive"))
    )
    (net (code "36") (name "37") (class "Default")
      (node (ref "ARDUINO_DUE1") (pin "37") (pinfunction "37_37") (pintype "bidirectional"))
      (node (ref "Q1") (pin "E") (pinfunction "E_E") (pintype "passive"))
      (node (ref "R38") (pin "2") (pinfunction "2_2") (pintype "passive"))
    )
    (net (code "37") (name "38") (class "Default")
      (node (ref "ARDUINO_DUE1") (pin "38") (pinfunction "38_38") (pintype "bidirectional"))
      (node (ref "JP16") (pin "8") (pinfunction "8_8") (pintype "passive"))
    )
    (net (code "38") (name "39") (class "Default")
      (node (ref "ARDUINO_DUE1") (pin "39") (pinfunction "39_39") (pintype "bidirectional"))
      (node (ref "Q9") (pin "E") (pinfunction "E_E") (pintype "passive"))
      (node (ref "R62") (pin "2") (pinfunction "2_2") (pintype "passive"))
    )
    (net (code "39") (name "40") (class "Default")
      (node (ref "ARDUINO_DUE1") (pin "40") (pinfunction "40_40") (pintype "bidirectional"))
      (node (ref "JP16") (pin "9") (pinfunction "9_9") (pintype "passive"))
    )
    (net (code "40") (name "41") (class "Default")
      (node (ref "ARDUINO_DUE1") (pin "41") (pinfunction "41_41") (pintype "bidirectional"))
      (node (ref "Q10") (pin "E") (pinfunction "E_E") (pintype "passive"))
      (node (ref "R59") (pin "2") (pinfunction "2_2") (pintype "passive"))
    )
    (net (code "41") (name "42") (class "Default")
      (node (ref "ARDUINO_DUE1") (pin "42") (pinfunction "42_42") (pintype "bidirectional"))
      (node (ref "JP16") (pin "10") (pinfunction "10_10") (pintype "passive"))
    )
    (net (code "42") (name "43") (class "Default")
      (node (ref "ARDUINO_DUE1") (pin "43") (pinfunction "43_43") (pintype "bidirectional"))
      (node (ref "Q11") (pin "E") (pinfunction "E_E") (pintype "passive"))
      (node (ref "R68") (pin "2") (pinfunction "2_2") (pintype "passive"))
    )
    (net (code "43") (name "44") (class "Default")
      (node (ref "ARDUINO_DUE1") (pin "44") (pinfunction "44_44") (pintype "bidirectional"))
      (node (ref "JP16") (pin "11") (pinfunction "11_11") (pintype "passive"))
    )
    (net (code "44") (name "45") (class "Default")
      (node (ref "ARDUINO_DUE1") (pin "45") (pinfunction "45_45") (pintype "bidirectional"))
      (node (ref "Q12") (pin "E") (pinfunction "E_E") (pintype "passive"))
      (node (ref "R65") (pin "2") (pinfunction "2_2") (pintype "passive"))
    )
    (net (code "45") (name "46") (class "Default")
      (node (ref "ARDUINO_DUE1") (pin "46") (pinfunction "46_46") (pintype "bidirectional"))
      (node (ref "JP8") (pin "1") (pinfunction "1_1") (pintype "passive"))
    )
    (net (code "46") (name "47") (class "Default")
      (node (ref "ARDUINO_DUE1") (pin "47") (pinfunction "47_47") (pintype "bidirectional"))
      (node (ref "IC2") (pin "4") (pinfunction "I4_4") (pintype "input"))
    )
    (net (code "47") (name "48") (class "Default")
      (node (ref "ARDUINO_DUE1") (pin "48") (pinfunction "48_48") (pintype "bidirectional"))
      (node (ref "JP8") (pin "3") (pinfunction "3_3") (pintype "passive"))
    )
    (net (code "48") (name "49") (class "Default")
      (node (ref "ARDUINO_DUE1") (pin "49") (pinfunction "49_49") (pintype "bidirectional"))
      (node (ref "IC2") (pin "3") (pinfunction "I3_3") (pintype "input"))
    )
    (net (code "49") (name "50") (class "Default")
      (node (ref "ARDUINO_DUE1") (pin "50") (pinfunction "50_50") (pintype "bidirectional"))
      (node (ref "JP11") (pin "1") (pinfunction "1_1") (pintype "passive"))
    )
    (net (code "50") (name "51") (class "Default")
      (node (ref "ARDUINO_DUE1") (pin "51") (pinfunction "51_51") (pintype "bidirectional"))
      (node (ref "IC2") (pin "2") (pinfunction "I2_2") (pintype "input"))
    )
    (net (code "51") (name "52") (class "Default")
      (node (ref "ARDUINO_DUE1") (pin "52") (pinfunction "52_52") (pintype "bidirectional"))
      (node (ref "JP11") (pin "3") (pinfunction "3_3") (pintype "passive"))
    )
    (net (code "52") (name "53") (class "Default")
      (node (ref "ARDUINO_DUE1") (pin "53") (pinfunction "53_53") (pintype "bidirectional"))
      (node (ref "IC2") (pin "1") (pinfunction "I1_1") (pintype "input"))
    )
    (net (code "53") (name "222") (class "Default")
      (node (ref "F2") (pin "2") (pinfunction "2_2") (pintype "passive"))
      (node (ref "X2") (pin "2") (pinfunction "KL_2") (pintype "passive"))
    )
    (net (code "54") (name "333") (class "Default")
      (node (ref "F3") (pin "2") (pinfunction "2_2") (pintype "passive"))
      (node (ref "X5") (pin "1") (pinfunction "KL_1") (pintype "passive"))
    )
    (net (code "55") (name "444") (class "Default")
      (node (ref "F4") (pin "2") (pinfunction "2_2") (pintype "passive"))
      (node (ref "X1") (pin "2") (pinfunction "KL_2") (pintype "passive"))
    )
    (net (code "56") (name "555") (class "Default")
      (node (ref "F5") (pin "2") (pinfunction "2_2") (pintype "passive"))
      (node (ref "X4") (pin "1") (pinfunction "KL_1") (pintype "passive"))
    )
    (net (code "57") (name "A0") (class "Default")
      (node (ref "ARDUINO_DUE1") (pin "A0") (pinfunction "AN0_A0") (pintype "bidirectional"))
      (node (ref "IC3") (pin "1") (pinfunction "I1_1") (pintype "input"))
    )
    (net (code "58") (name "A1") (class "Default")
      (node (ref "ARDUINO_DUE1") (pin "A1") (pinfunction "AN1_A1") (pintype "bidirectional"))
      (node (ref "IC3") (pin "2") (pinfunction "I2_2") (pintype "input"))
    )
    (net (code "59") (name "A2") (class "Default")
      (node (ref "ARDUINO_DUE1") (pin "A2") (pinfunction "AN2_A2") (pintype "bidirectional"))
      (node (ref "IC3") (pin "3") (pinfunction "I3_3") (pintype "input"))
    )
    (net (code "60") (name "A3") (class "Default")
      (node (ref "ARDUINO_DUE1") (pin "A3") (pinfunction "AN3_A3") (pintype "bidirectional"))
      (node (ref "IC3") (pin "4") (pinfunction "I4_4") (pintype "input"))
    )
    (net (code "61") (name "A4") (class "Default")
      (node (ref "ARDUINO_DUE1") (pin "A4") (pinfunction "AN4_A4") (pintype "bidirectional"))
      (node (ref "JP3") (pin "4") (pinfunction "4_4") (pintype "passive"))
    )
    (net (code "62") (name "A5") (class "Default")
      (node (ref "ARDUINO_DUE1") (pin "A5") (pinfunction "AN5_A5") (pintype "bidirectional"))
      (node (ref "JP3") (pin "3") (pinfunction "3_3") (pintype "passive"))
    )
    (net (code "63") (name "A6") (class "Default")
      (node (ref "ARDUINO_DUE1") (pin "A6") (pinfunction "AN6_A6") (pintype "bidirectional"))
      (node (ref "JP3") (pin "2") (pinfunction "2_2") (pintype "passive"))
    )
    (net (code "64") (name "A7") (class "Default")
      (node (ref "ARDUINO_DUE1") (pin "A7") (pinfunction "AN7_A7") (pintype "bidirectional"))
      (node (ref "JP3") (pin "1") (pinfunction "1_1") (pintype "passive"))
    )
    (net (code "65") (name "A8") (class "Default")
      (node (ref "ARDUINO_DUE1") (pin "A8") (pinfunction "AN8_A8") (pintype "bidirectional"))
      (node (ref "JP15") (pin "8") (pinfunction "8_8") (pintype "passive"))
    )
    (net (code "66") (name "A9") (class "Default")
      (node (ref "ARDUINO_DUE1") (pin "A9") (pinfunction "AN9_A9") (pintype "bidirectional"))
      (node (ref "JP15") (pin "7") (pinfunction "7_7") (pintype "passive"))
    )
    (net (code "67") (name "A10") (class "Default")
      (node (ref "ARDUINO_DUE1") (pin "A10") (pinfunction "AN10_A10") (pintype "bidirectional"))
      (node (ref "JP15") (pin "6") (pinfunction "6_6") (pintype "passive"))
    )
    (net (code "68") (name "A11") (class "Default")
      (node (ref "ARDUINO_DUE1") (pin "A11") (pinfunction "AN11_A11") (pintype "bidirectional"))
      (node (ref "JP15") (pin "5") (pinfunction "5_5") (pintype "passive"))
    )
    (net (code "69") (name "CANRX") (class "Default")
      (node (ref "ARDUINO_DUE1") (pin "CANRX") (pinfunction "CANRX_CANRX") (pintype "bidirectional"))
      (node (ref "JP15") (pin "2") (pinfunction "2_2") (pintype "passive"))
    )
    (net (code "70") (name "CANTX") (class "Default")
      (node (ref "ARDUINO_DUE1") (pin "CANTX") (pinfunction "CANTX_CANTX") (pintype "bidirectional"))
      (node (ref "JP15") (pin "1") (pinfunction "1_1") (pintype "passive"))
    )
    (net (code "71") (name "D") (class "Default")
      (node (ref "F1") (pin "2") (pinfunction "2_2") (pintype "passive"))
      (node (ref "F2") (pin "1") (pinfunction "1_1") (pintype "passive"))
      (node (ref "F3") (pin "1") (pinfunction "1_1") (pintype "passive"))
      (node (ref "F4") (pin "1") (pinfunction "1_1") (pintype "passive"))
      (node (ref "F5") (pin "1") (pinfunction "1_1") (pintype "passive"))
    )
    (net (code "72") (name "DAC0") (class "Default")
      (node (ref "ARDUINO_DUE1") (pin "DAC0") (pinfunction "DAC0_DAC0") (pintype "bidirectional"))
      (node (ref "JP15") (pin "4") (pinfunction "4_4") (pintype "passive"))
    )
    (net (code "73") (name "DAC1") (class "Default")
      (node (ref "ARDUINO_DUE1") (pin "DAC1") (pinfunction "DAC1_DAC1") (pintype "bidirectional"))
      (node (ref "JP15") (pin "3") (pinfunction "3_3") (pintype "passive"))
    )
    (net (code "74") (name "EN1") (class "Default")
      (node (ref "JP2") (pin "3") (pinfunction "3_3") (pintype "passive"))
      (node (ref "R36") (pin "1") (pinfunction "1_1") (pintype "passive"))
      (node (ref "R37") (pin "1") (pinfunction "1_1") (pintype "passive"))
    )
    (net (code "75") (name "EN2") (class "Default")
      (node (ref "JP2") (pin "4") (pinfunction "4_4") (pintype "passive"))
      (node (ref "R33") (pin "1") (pinfunction "1_1") (pintype "passive"))
      (node (ref "R34") (pin "1") (pinfunction "1_1") (pintype "passive"))
    )
    (net (code "76") (name "EN3") (class "Default")
      (node (ref "JP1") (pin "3") (pinfunction "3_3") (pintype "passive"))
      (node (ref "R42") (pin "1") (pinfunction "1_1") (pintype "passive"))
      (node (ref "R43") (pin "1") (pinfunction "1_1") (pintype "passive"))
    )
    (net (code "77") (name "EN4") (class "Default")
      (node (ref "JP1") (pin "4") (pinfunction "4_4") (pintype "passive"))
      (node (ref "R39") (pin "1") (pinfunction "1_1") (pintype "passive"))
      (node (ref "R40") (pin "1") (pinfunction "1_1") (pintype "passive"))
    )
    (net (code "78") (name "EN9") (class "Default")
      (node (ref "JP7") (pin "3") (pinfunction "3_3") (pintype "passive"))
      (node (ref "R60") (pin "1") (pinfunction "1_1") (pintype "passive"))
      (node (ref "R61") (pin "1") (pinfunction "1_1") (pintype "passive"))
    )
    (net (code "79") (name "EN10") (class "Default")
      (node (ref "JP7") (pin "4") (pinfunction "4_4") (pintype "passive"))
      (node (ref "R57") (pin "1") (pinfunction "1_1") (pintype "passive"))
      (node (ref "R58") (pin "1") (pinfunction "1_1") (pintype "passive"))
    )
    (net (code "80") (name "EN11") (class "Default")
      (node (ref "JP5") (pin "3") (pinfunction "3_3") (pintype "passive"))
      (node (ref "R66") (pin "1") (pinfunction "1_1") (pintype "passive"))
      (node (ref "R67") (pin "1") (pinfunction "1_1") (pintype "passive"))
    )
    (net (code "81") (name "EN12") (class "Default")
      (node (ref "JP5") (pin "4") (pinfunction "4_4") (pintype "passive"))
      (node (ref "R63") (pin "1") (pinfunction "1_1") (pintype "passive"))
      (node (ref "R64") (pin "1") (pinfunction "1_1") (pintype "passive"))
    )
    (net (code "82") (name "ENABLE") (class "Default")
      (node (ref "U$2") (pin "6") (pinfunction "EN_6") (pintype "bidirectional"))
    )
    (net (code "83") (name "GNND") (class "Default")
      (node (ref "1-1") (pin "GND") (pinfunction "GND_GND") (pintype "input"))
      (node (ref "1-2") (pin "GND") (pinfunction "GND_GND") (pintype "input"))
      (node (ref "1-7805") (pin "GND") (pinfunction "GND_GND") (pintype "input"))
      (node (ref "1-7809") (pin "GND") (pinfunction "GND_GND") (pintype "input"))
      (node (ref "2-7805") (pin "GND") (pinfunction "GND_GND") (pintype "input"))
      (node (ref "2-7809") (pin "GND") (pinfunction "GND_GND") (pintype "input"))
      (node (ref "ARDUINO_DUE1") (pin "GND_1") (pinfunction "GND_GND_1") (pintype "bidirectional"))
      (node (ref "ARDUINO_DUE1") (pin "GND_3") (pinfunction "GND_GND_3") (pintype "bidirectional"))
      (node (ref "C1") (pin "-") (pinfunction "-_-") (pintype "passive"))
      (node (ref "C2") (pin "2") (pinfunction "2_2") (pintype "passive"))
      (node (ref "C3") (pin "-") (pinfunction "-_-") (pintype "passive"))
      (node (ref "C4") (pin "-") (pinfunction "-_-") (pintype "passive"))
      (node (ref "C5") (pin "2") (pinfunction "2_2") (pintype "passive"))
      (node (ref "C6") (pin "-") (pinfunction "-_-") (pintype "passive"))
      (node (ref "GND") (pin "1") (pinfunction "1_1") (pintype "passive"))
      (node (ref "GND") (pin "2") (pinfunction "2_2") (pintype "passive"))
      (node (ref "GND") (pin "3") (pinfunction "3_3") (pintype "passive"))
      (node (ref "GND") (pin "4") (pinfunction "4_4") (pintype "passive"))
      (node (ref "GND") (pin "5") (pinfunction "5_5") (pintype "passive"))
      (node (ref "GND1") (pin "1") (pinfunction "1_1") (pintype "passive"))
      (node (ref "GND1") (pin "2") (pinfunction "2_2") (pintype "passive"))
      (node (ref "GND1") (pin "3") (pinfunction "3_3") (pintype "passive"))
      (node (ref "GND1") (pin "4") (pinfunction "4_4") (pintype "passive"))
      (node (ref "GND1") (pin "5") (pinfunction "5_5") (pintype "passive"))
      (node (ref "IC1") (pin "8") (pinfunction "GND_8") (pintype "power_in"))
      (node (ref "IC2") (pin "8") (pinfunction "GND_8") (pintype "power_in"))
      (node (ref "IC3") (pin "8") (pinfunction "GND_8") (pintype "power_in"))
      (node (ref "JP1") (pin "2") (pinfunction "2_2") (pintype "passive"))
      (node (ref "JP11") (pin "5") (pinfunction "5_5") (pintype "passive"))
      (node (ref "JP13") (pin "5") (pinfunction "5_5") (pintype "passive"))
      (node (ref "JP2") (pin "2") (pinfunction "2_2") (pintype "passive"))
      (node (ref "JP4") (pin "5") (pinfunction "5_5") (pintype "passive"))
      (node (ref "JP5") (pin "2") (pinfunction "2_2") (pintype "passive"))
      (node (ref "JP7") (pin "2") (pinfunction "2_2") (pintype "passive"))
      (node (ref "JP8") (pin "5") (pinfunction "5_5") (pintype "passive"))
      (node (ref "MAIN_POWER") (pin "1") (pinfunction "KL_1") (pintype "passive"))
      (node (ref "R1") (pin "1") (pinfunction "1_1") (pintype "passive"))
      (node (ref "R2") (pin "1") (pinfunction "1_1") (pintype "passive"))
      (node (ref "R3") (pin "1") (pinfunction "1_1") (pintype "passive"))
      (node (ref "R35") (pin "1") (pinfunction "1_1") (pintype "passive"))
      (node (ref "R38") (pin "1") (pinfunction "1_1") (pintype "passive"))
      (node (ref "R4") (pin "1") (pinfunction "1_1") (pintype "passive"))
      (node (ref "R41") (pin "1") (pinfunction "1_1") (pintype "passive"))
      (node (ref "R44") (pin "1") (pinfunction "1_1") (pintype "passive"))
      (node (ref "R5") (pin "1") (pinfunction "1_1") (pintype "passive"))
      (node (ref "R59") (pin "1") (pinfunction "1_1") (pintype "passive"))
      (node (ref "R6") (pin "1") (pinfunction "1_1") (pintype "passive"))
      (node (ref "R62") (pin "1") (pinfunction "1_1") (pintype "passive"))
      (node (ref "R65") (pin "1") (pinfunction "1_1") (pintype "passive"))
      (node (ref "R68") (pin "1") (pinfunction "1_1") (pintype "passive"))
      (node (ref "U$1") (pin "GND1") (pinfunction "GND1_GND1") (pintype "bidirectional"))
      (node (ref "U$2") (pin "4") (pinfunction "GND_4") (pintype "power_in"))
      (node (ref "X1") (pin "1") (pinfunction "KL_1") (pintype "passive"))
      (node (ref "X2") (pin "1") (pinfunction "KL_1") (pintype "passive"))
      (node (ref "X4") (pin "2") (pinfunction "KL_2") (pintype "passive"))
      (node (ref "X5") (pin "2") (pinfunction "KL_2") (pintype "passive"))
      (node (ref "X6") (pin "GND") (pinfunction "GND_GND") (pintype "bidirectional"))
      (node (ref "X7") (pin "GND") (pinfunction "GND_GND") (pintype "bidirectional"))
    )
    (net (code "84") (name "N$15") (class "Default")
      (node (ref "ARDUINO_DUE1") (pin "GND_2") (pinfunction "GND_GND_2") (pintype "bidirectional"))
    )
    (net (code "85") (name "N$50") (class "Default")
      (node (ref "ARDUINO_DUE1") (pin "5V0_2") (pinfunction "5V_5V0_2") (pintype "bidirectional"))
    )
    (net (code "86") (name "N$65") (class "Default")
      (node (ref "ARDUINO_DUE1") (pin "14") (pinfunction "TX3_14_14") (pintype "bidirectional"))
    )
    (net (code "87") (name "N$66") (class "Default")
      (node (ref "ARDUINO_DUE1") (pin "15") (pinfunction "RX3_15_15") (pintype "bidirectional"))
    )
    (net (code "88") (name "N$67") (class "Default")
      (node (ref "ARDUINO_DUE1") (pin "16") (pinfunction "TX2_16_16") (pintype "bidirectional"))
    )
    (net (code "89") (name "N$68") (class "Default")
      (node (ref "ARDUINO_DUE1") (pin "17") (pinfunction "RX2_17_17") (pintype "bidirectional"))
    )
    (net (code "90") (name "N$69") (class "Default")
      (node (ref "ARDUINO_DUE1") (pin "18") (pinfunction "TX1_18_18") (pintype "bidirectional"))
    )
    (net (code "91") (name "N$70") (class "Default")
      (node (ref "ARDUINO_DUE1") (pin "19") (pinfunction "RX1_19_19") (pintype "bidirectional"))
    )
    (net (code "92") (name "N$71") (class "Default")
      (node (ref "ARDUINO_DUE1") (pin "20") (pinfunction "SDA_20_20") (pintype "bidirectional"))
    )
    (net (code "93") (name "N$72") (class "Default")
      (node (ref "ARDUINO_DUE1") (pin "21") (pinfunction "SCL_21_21") (pintype "bidirectional"))
    )
    (net (code "94") (name "N$73") (class "Default")
      (node (ref "ARDUINO_DUE1") (pin "SCL1") (pinfunction "SCL1_SCL1") (pintype "bidirectional"))
    )
    (net (code "95") (name "N$74") (class "Default")
      (node (ref "ARDUINO_DUE1") (pin "SDA1") (pinfunction "SDA1_SDA1") (pintype "bidirectional"))
    )
    (net (code "96") (name "N$75") (class "Default")
      (node (ref "ARDUINO_DUE1") (pin "AREF") (pinfunction "AREF_AREF") (pintype "bidirectional"))
    )
    (net (code "97") (name "N$76") (class "Default")
      (node (ref "ARDUINO_DUE1") (pin "GND_4") (pinfunction "GND_GND_4") (pintype "bidirectional"))
    )
    (net (code "99") (name "N$78") (class "Default")
      (node (ref "ARDUINO_DUE1") (pin "IOREF") (pinfunction "IOREF_IOREF") (pintype "bidirectional"))
    )
    (net (code "100") (name "N$79") (class "Default")
      (node (ref "ARDUINO_DUE1") (pin "RESET") (pinfunction "RESET_RESET") (pintype "bidirectional"))
    )
    (net (code "101") (name "N$82") (class "Default")
      (node (ref "ARDUINO_DUE1") (pin "GND") (pinfunction "GND_GND") (pintype "bidirectional"))
    )
    (net (code "102") (name "Net-(1-7805-PadIN)") (class "Default")
      (node (ref "1-7805") (pin "IN") (pinfunction "IN_IN") (pintype "input"))
      (node (ref "1-7809") (pin "OUT") (pinfunction "OUT_OUT") (pintype "passive"))
      (node (ref "C3") (pin "+") (pinfunction "+_+") (pintype "passive"))
      (node (ref "LED3") (pin "A") (pinfunction "A_A") (pintype "passive"))
    )
    (net (code "103") (name "Net-(2-7805-PadIN)") (class "Default")
      (node (ref "2-7805") (pin "IN") (pinfunction "IN_IN") (pintype "input"))
      (node (ref "2-7809") (pin "OUT") (pinfunction "OUT_OUT") (pintype "passive"))
      (node (ref "C6") (pin "+") (pinfunction "+_+") (pintype "passive"))
      (node (ref "LED5") (pin "A") (pinfunction "A_A") (pintype "passive"))
    )
    (net (code "104") (name "Net-(C2-Pad1)") (class "Default")
      (node (ref "C2") (pin "1") (pinfunction "1_1") (pintype "passive"))
      (node (ref "LED2") (pin "A") (pinfunction "A_A") (pintype "passive"))
    )
    (net (code "105") (name "Net-(LED1-C)") (class "Default")
      (node (ref "LED1") (pin "K") (pinfunction "C_K") (pintype "passive"))
      (node (ref "R1") (pin "2") (pinfunction "2_2") (pintype "passive"))
    )
    (net (code "106") (name "Net-(LED2-C)") (class "Default")
      (node (ref "LED2") (pin "K") (pinfunction "C_K") (pintype "passive"))
      (node (ref "R2") (pin "2") (pinfunction "2_2") (pintype "passive"))
    )
    (net (code "107") (name "Net-(LED3-C)") (class "Default")
      (node (ref "LED3") (pin "K") (pinfunction "C_K") (pintype "passive"))
      (node (ref "R4") (pin "2") (pinfunction "2_2") (pintype "passive"))
    )
    (net (code "108") (name "Net-(LED4-C)") (class "Default")
      (node (ref "LED4") (pin "K") (pinfunction "C_K") (pintype "passive"))
      (node (ref "R3") (pin "2") (pinfunction "2_2") (pintype "passive"))
    )
    (net (code "109") (name "Net-(LED5-C)") (class "Default")
      (node (ref "LED5") (pin "K") (pinfunction "C_K") (pintype "passive"))
      (node (ref "R5") (pin "2") (pinfunction "2_2") (pintype "passive"))
    )
    (net (code "110") (name "Net-(LED6-C)") (class "Default")
      (node (ref "LED6") (pin "K") (pinfunction "C_K") (pintype "passive"))
      (node (ref "R6") (pin "2") (pinfunction "2_2") (pintype "passive"))
    )
    (net (code "111") (name "Net-(LED7-C)") (class "Default")
      (node (ref "LED7") (pin "K") (pinfunction "C_K") (pintype "passive"))
      (node (ref "R7") (pin "2") (pinfunction "2_2") (pintype "passive"))
    )
    (net (code "112") (name "Net-(LED8-C)") (class "Default")
      (node (ref "LED8") (pin "K") (pinfunction "C_K") (pintype "passive"))
      (node (ref "R8") (pin "2") (pinfunction "2_2") (pintype "passive"))
    )
    (net (code "113") (name "Net-(LED9-C)") (class "Default")
      (node (ref "LED9") (pin "K") (pinfunction "C_K") (pintype "passive"))
      (node (ref "R9") (pin "2") (pinfunction "2_2") (pintype "passive"))
    )
    (net (code "114") (name "Net-(LED10-C)") (class "Default")
      (node (ref "LED10") (pin "K") (pinfunction "C_K") (pintype "passive"))
      (node (ref "R10") (pin "2") (pinfunction "2_2") (pintype "passive"))
    )
    (net (code "115") (name "Net-(LED11-C)") (class "Default")
      (node (ref "LED11") (pin "K") (pinfunction "C_K") (pintype "passive"))
      (node (ref "R11") (pin "2") (pinfunction "2_2") (pintype "passive"))
    )
    (net (code "116") (name "Net-(LED12-C)") (class "Default")
      (node (ref "LED12") (pin "K") (pinfunction "C_K") (pintype "passive"))
      (node (ref "R12") (pin "2") (pinfunction "2_2") (pintype "passive"))
    )
    (net (code "117") (name "Net-(LED13-C)") (class "Default")
      (node (ref "LED13") (pin "K") (pinfunction "C_K") (pintype "passive"))
      (node (ref "R13") (pin "2") (pinfunction "2_2") (pintype "passive"))
    )
    (net (code "118") (name "Net-(LED14-C)") (class "Default")
      (node (ref "LED14") (pin "K") (pinfunction "C_K") (pintype "passive"))
      (node (ref "R14") (pin "2") (pinfunction "2_2") (pintype "passive"))
    )
    (net (code "119") (name "Net-(Q1-PadB)") (class "Default")
      (node (ref "Q1") (pin "B") (pinfunction "B_B") (pintype "passive"))
      (node (ref "R36") (pin "2") (pinfunction "2_2") (pintype "passive"))
    )
    (net (code "120") (name "Net-(Q2-PadB)") (class "Default")
      (node (ref "Q2") (pin "B") (pinfunction "B_B") (pintype "passive"))
      (node (ref "R33") (pin "2") (pinfunction "2_2") (pintype "passive"))
    )
    (net (code "121") (name "Net-(Q3-PadB)") (class "Default")
      (node (ref "Q3") (pin "B") (pinfunction "B_B") (pintype "passive"))
      (node (ref "R42") (pin "2") (pinfunction "2_2") (pintype "passive"))
    )
    (net (code "122") (name "Net-(Q4-PadB)") (class "Default")
      (node (ref "Q4") (pin "B") (pinfunction "B_B") (pintype "passive"))
      (node (ref "R39") (pin "2") (pinfunction "2_2") (pintype "passive"))
    )
    (net (code "123") (name "Net-(Q9-PadB)") (class "Default")
      (node (ref "Q9") (pin "B") (pinfunction "B_B") (pintype "passive"))
      (node (ref "R60") (pin "2") (pinfunction "2_2") (pintype "passive"))
    )
    (net (code "124") (name "Net-(Q10-PadB)") (class "Default")
      (node (ref "Q10") (pin "B") (pinfunction "B_B") (pintype "passive"))
      (node (ref "R57") (pin "2") (pinfunction "2_2") (pintype "passive"))
    )
    (net (code "125") (name "Net-(Q11-PadB)") (class "Default")
      (node (ref "Q11") (pin "B") (pinfunction "B_B") (pintype "passive"))
      (node (ref "R66") (pin "2") (pinfunction "2_2") (pintype "passive"))
    )
    (net (code "126") (name "Net-(Q12-PadB)") (class "Default")
      (node (ref "Q12") (pin "B") (pinfunction "B_B") (pintype "passive"))
      (node (ref "R63") (pin "2") (pinfunction "2_2") (pintype "passive"))
    )
    (net (code "127") (name "O1") (class "Default")
      (node (ref "IC1") (pin "16") (pinfunction "O1_16") (pintype "open_collector"))
      (node (ref "LED7") (pin "A") (pinfunction "A_A") (pintype "passive"))
      (node (ref "X3") (pin "1") (pinfunction "KL_1") (pintype "passive"))
    )
    (net (code "128") (name "O2") (class "Default")
      (node (ref "IC1") (pin "15") (pinfunction "O2_15") (pintype "open_collector"))
      (node (ref "LED9") (pin "A") (pinfunction "A_A") (pintype "passive"))
      (node (ref "X10") (pin "1") (pinfunction "KL_1") (pintype "passive"))
    )
    (net (code "129") (name "O3") (class "Default")
      (node (ref "IC1") (pin "14") (pinfunction "O3_14") (pintype "open_collector"))
      (node (ref "LED8") (pin "A") (pinfunction "A_A") (pintype "passive"))
      (node (ref "X8") (pin "1") (pinfunction "KL_1") (pintype "passive"))
    )
    (net (code "130") (name "O4") (class "Default")
      (node (ref "IC1") (pin "13") (pinfunction "O4_13") (pintype "open_collector"))
      (node (ref "LED10") (pin "A") (pinfunction "A_A") (pintype "passive"))
      (node (ref "X9") (pin "1") (pinfunction "KL_1") (pintype "passive"))
    )
    (net (code "131") (name "O5") (class "Default")
      (node (ref "IC2") (pin "16") (pinfunction "O1_16") (pintype "open_collector"))
      (node (ref "LED12") (pin "A") (pinfunction "A_A") (pintype "passive"))
      (node (ref "X11") (pin "1") (pinfunction "KL_1") (pintype "passive"))
    )
    (net (code "132") (name "O6") (class "Default")
      (node (ref "IC2") (pin "15") (pinfunction "O2_15") (pintype "open_collector"))
      (node (ref "LED13") (pin "A") (pinfunction "A_A") (pintype "passive"))
      (node (ref "X14") (pin "2") (pinfunction "KL_2") (pintype "passive"))
    )
    (net (code "133") (name "O7") (class "Default")
      (node (ref "IC2") (pin "14") (pinfunction "O3_14") (pintype "open_collector"))
      (node (ref "LED11") (pin "A") (pinfunction "A_A") (pintype "passive"))
      (node (ref "X12") (pin "1") (pinfunction "KL_1") (pintype "passive"))
    )
    (net (code "134") (name "O8") (class "Default")
      (node (ref "IC2") (pin "13") (pinfunction "O4_13") (pintype "open_collector"))
      (node (ref "LED14") (pin "A") (pinfunction "A_A") (pintype "passive"))
      (node (ref "X13") (pin "2") (pinfunction "KL_2") (pintype "passive"))
    )
    (net (code "135") (name "O9") (class "Default")
      (node (ref "IC3") (pin "16") (pinfunction "O1_16") (pintype "open_collector"))
      (node (ref "X15") (pin "1") (pinfunction "KL_1") (pintype "passive"))
    )
    (net (code "136") (name "O10") (class "Default")
      (node (ref "IC3") (pin "15") (pinfunction "O2_15") (pintype "open_collector"))
      (node (ref "X16") (pin "1") (pinfunction "KL_1") (pintype "passive"))
    )
    (net (code "137") (name "O11") (class "Default")
      (node (ref "IC3") (pin "14") (pinfunction "O3_14") (pintype "open_collector"))
      (node (ref "X17") (pin "1") (pinfunction "KL_1") (pintype "passive"))
    )
    (net (code "138") (name "O12") (class "Default")
      (node (ref "IC3") (pin "13") (pinfunction "O4_13") (pintype "open_collector"))
      (node (ref "X18") (pin "1") (pinfunction "KL_1") (pintype "passive"))
    )
    (net (code "139") (name "RX0") (class "Default")
      (node (ref "ARDUINO_DUE1") (pin "0") (pinfunction "RX0<0_0") (pintype "bidirectional"))
      (node (ref "U$2") (pin "3") (pinfunction "TX_3") (pintype "bidirectional"))
    )
    (net (code "140") (name "STATE") (class "Default")
      (node (ref "U$2") (pin "1") (pinfunction "STATE_1") (pintype "bidirectional"))
    )
    (net (code "141") (name "TX0") (class "Default")
      (node (ref "ARDUINO_DUE1") (pin "1") (pinfunction "TX0>1_1") (pintype "bidirectional"))
      (node (ref "U$2") (pin "2") (pinfunction "RX_2") (pintype "bidirectional"))
    )
    (net (code "142") (name "VCC") (class "Default")
      (node (ref "2-7805") (pin "OUT") (pinfunction "OUT_OUT") (pintype "passive"))
      (node (ref "C4") (pin "+") (pinfunction "+_+") (pintype "passive"))
      (node (ref "JP5") (pin "1") (pinfunction "1_1") (pintype "passive"))
      (node (ref "JP7") (pin "1") (pinfunction "1_1") (pintype "passive"))
      (node (ref "LED6") (pin "A") (pinfunction "A_A") (pintype "passive"))
      (node (ref "R58") (pin "2") (pinfunction "2_2") (pintype "passive"))
      (node (ref "R61") (pin "2") (pinfunction "2_2") (pintype "passive"))
      (node (ref "R64") (pin "2") (pinfunction "2_2") (pintype "passive"))
      (node (ref "R67") (pin "2") (pinfunction "2_2") (pintype "passive"))
    )
    (net (code "143") (name "VCC1") (class "Default")
      (node (ref "1-7805") (pin "OUT") (pinfunction "OUT_OUT") (pintype "passive"))
      (node (ref "C5") (pin "1") (pinfunction "1_1") (pintype "passive"))
      (node (ref "JP1") (pin "1") (pinfunction "1_1") (pintype "passive"))
      (node (ref "JP2") (pin "1") (pinfunction "1_1") (pintype "passive"))
      (node (ref "LED4") (pin "A") (pinfunction "A_A") (pintype "passive"))
      (node (ref "R34") (pin "2") (pinfunction "2_2") (pintype "passive"))
      (node (ref "R37") (pin "2") (pinfunction "2_2") (pintype "passive"))
      (node (ref "R40") (pin "2") (pinfunction "2_2") (pintype "passive"))
      (node (ref "R43") (pin "2") (pinfunction "2_2") (pintype "passive"))
      (node (ref "U$1") (pin "VIN") (pinfunction "VIN_VIN") (pintype "bidirectional"))
      (node (ref "VCC_REG") (pin "1") (pinfunction "1_1") (pintype "passive"))
      (node (ref "VCC_REG") (pin "2") (pinfunction "2_2") (pintype "passive"))
      (node (ref "VCC_REG") (pin "3") (pinfunction "3_3") (pintype "passive"))
      (node (ref "VCC_REG") (pin "4") (pinfunction "4_4") (pintype "passive"))
      (node (ref "VCC_REG") (pin "5") (pinfunction "5_5") (pintype "passive"))
    )
    (net (code "144") (name "VCC2") (class "Default")
      (node (ref "1-2") (pin "OUT") (pinfunction "OUT_OUT") (pintype "passive"))
      (node (ref "X6") (pin "VBUS") (pinfunction "VBUS_VBUS") (pintype "bidirectional"))
      (node (ref "X7") (pin "VBUS") (pinfunction "VBUS_VBUS") (pintype "bidirectional"))
    )
    (net (code "145") (name "unconnected-(ARDUINO_DUE1-NC-PadNC_2)") (class "Default")
      (node (ref "ARDUINO_DUE1") (pin "NC_2") (pinfunction "NC_NC_2") (pintype "no_connect"))
    )
    (net (code "146") (name "unconnected-(IC1-I5-Pad5)") (class "Default")
      (node (ref "IC1") (pin "5") (pinfunction "I5_5") (pintype "input"))
    )
    (net (code "147") (name "unconnected-(IC1-I6-Pad6)") (class "Default")
      (node (ref "IC1") (pin "6") (pinfunction "I6_6") (pintype "input"))
    )
    (net (code "148") (name "unconnected-(IC1-I7-Pad7)") (class "Default")
      (node (ref "IC1") (pin "7") (pinfunction "I7_7") (pintype "input"))
    )
    (net (code "149") (name "unconnected-(IC1-O5-Pad12)") (class "Default")
      (node (ref "IC1") (pin "12") (pinfunction "O5_12") (pintype "open_collector"))
    )
    (net (code "150") (name "unconnected-(IC1-O6-Pad11)") (class "Default")
      (node (ref "IC1") (pin "11") (pinfunction "O6_11") (pintype "open_collector"))
    )
    (net (code "151") (name "unconnected-(IC1-O7-Pad10)") (class "Default")
      (node (ref "IC1") (pin "10") (pinfunction "O7_10") (pintype "open_collector"))
    )
    (net (code "152") (name "unconnected-(IC2-I5-Pad5)") (class "Default")
      (node (ref "IC2") (pin "5") (pinfunction "I5_5") (pintype "input"))
    )
    (net (code "153") (name "unconnected-(IC2-I6-Pad6)") (class "Default")
      (node (ref "IC2") (pin "6") (pinfunction "I6_6") (pintype "input"))
    )
    (net (code "154") (name "unconnected-(IC2-I7-Pad7)") (class "Default")
      (node (ref "IC2") (pin "7") (pinfunction "I7_7") (pintype "input"))
    )
    (net (code "155") (name "unconnected-(IC2-O5-Pad12)") (class "Default")
      (node (ref "IC2") (pin "12") (pinfunction "O5_12") (pintype "open_collector"))
    )
    (net (code "156") (name "unconnected-(IC2-O6-Pad11)") (class "Default")
      (node (ref "IC2") (pin "11") (pinfunction "O6_11") (pintype "open_collector"))
    )
    (net (code "157") (name "unconnected-(IC2-O7-Pad10)") (class "Default")
      (node (ref "IC2") (pin "10") (pinfunction "O7_10") (pintype "open_collector"))
    )
    (net (code "158") (name "unconnected-(IC3-I5-Pad5)") (class "Default")
      (node (ref "IC3") (pin "5") (pinfunction "I5_5") (pintype "input"))
    )
    (net (code "159") (name "unconnected-(IC3-I6-Pad6)") (class "Default")
      (node (ref "IC3") (pin "6") (pinfunction "I6_6") (pintype "input"))
    )
    (net (code "160") (name "unconnected-(IC3-I7-Pad7)") (class "Default")
      (node (ref "IC3") (pin "7") (pinfunction "I7_7") (pintype "input"))
    )
    (net (code "161") (name "unconnected-(IC3-O5-Pad12)") (class "Default")
      (node (ref "IC3") (pin "12") (pinfunction "O5_12") (pintype "open_collector"))
    )
    (net (code "162") (name "unconnected-(IC3-O6-Pad11)") (class "Default")
      (node (ref "IC3") (pin "11") (pinfunction "O6_11") (pintype "open_collector"))
    )
    (net (code "163") (name "unconnected-(IC3-O7-Pad10)") (class "Default")
      (node (ref "IC3") (pin "10") (pinfunction "O7_10") (pintype "open_collector"))
    )
    (net (code "164") (name "unconnected-(U$1-PadGND2)") (class "Default")
      (node (ref "U$1") (pin "GND2") (pinfunction "GND2_GND2") (pintype "bidirectional"))
    )
    (net (code "165") (name "unconnected-(X6-PadD+)") (class "Default")
      (node (ref "X6") (pin "D+") (pinfunction "D+_D+") (pintype "bidirectional"))
    )
    (net (code "166") (name "unconnected-(X6-PadD-)") (class "Default")
      (node (ref "X6") (pin "D-") (pinfunction "D-_D-") (pintype "bidirectional"))
    )
    (net (code "167") (name "unconnected-(X7-PadD+)") (class "Default")
      (node (ref "X7") (pin "D+") (pinfunction "D+_D+") (pintype "bidirectional"))
    )
    (net (code "168") (name "unconnected-(X7-PadD-)") (class "Default")
      (node (ref "X7") (pin "D-") (pinfunction "D-_D-") (pintype "bidirectional"))
    )
  )
)
